# atom-hub-proto-self-Vorlage.net
KiCad netlist of a schematic drawn in EAGLE
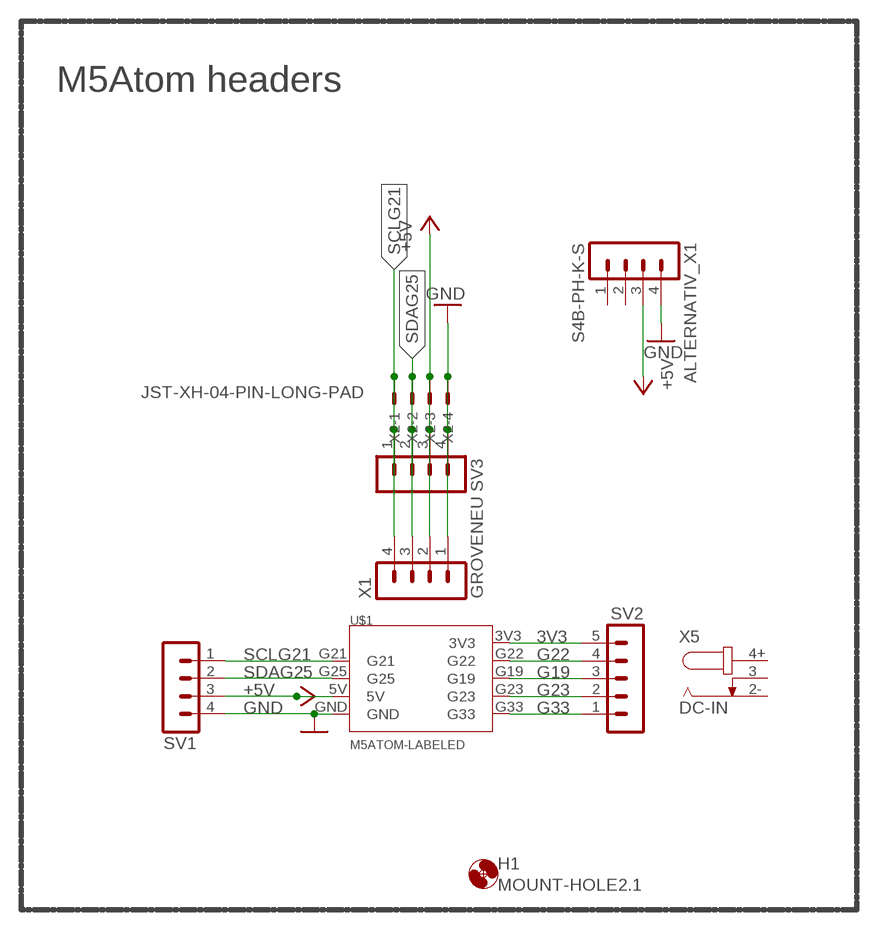
[diagram p0: schematic, sheet 1]

(export (version "E")
  (design (tool "Eeschema 10.0.6"))
  (components
    (comp (ref "ALTERNATIV_X1")
      (value "S4B-PH-K-S")
      (footprint "eagle-import:S4B-PH-K-S")
      (libsource (lib "eagle-import") (part "S4B-PH-K-S"))
    )
    (comp (ref "H1")
      (value "MOUNT-HOLE2.1")
      (footprint "eagle-import:2,1")
      (libsource (lib "eagle-import") (part "MOUNT-HOLE2.1"))
    )
    (comp (ref "SV1")
      (value "MA04-1")
      (footprint "eagle-import:MA04-1")
      (libsource (lib "eagle-import") (part "MA04-1"))
    )
    (comp (ref "SV2")
      (value "MA05-1")
      (footprint "eagle-import:MA05-1")
      (libsource (lib "eagle-import") (part "MA05-1"))
    )
    (comp (ref "SV3")
      (value "MA04-1")
      (footprint "eagle-import:MA04-1")
      (libsource (lib "eagle-import") (part "MA04-1"))
    )
    (comp (ref "U$1")
      (value "M5ATOM-LABELED")
      (footprint "eagle-import:M5ATOM-W_-LABELS")
      (libsource (lib "eagle-import") (part "M5ATOM-LABELED"))
    )
    (comp (ref "X1")
      (value "GROVENEU")
      (footprint "eagle-import:GROVE-NEU")
      (libsource (lib "eagle-import") (part "GROVENEU"))
    )
    (comp (ref "X2")
      (value "JST-XH-04-PIN-LONG-PAD")
      (footprint "eagle-import:JST-XH-04-PACKAGE-LONG-PAD")
      (libsource (lib "eagle-import") (part "JST-XH-04-PIN-LONG-PAD"))
    )
    (comp (ref "X5")
      (value "DC-IN")
      (footprint "eagle-import:DC-IN-TH_DC-0440-2.5A-2.0")
      (libsource (lib "eagle-import") (part "DC-IN"))
    )
  )
  (nets
    (net (code "1") (name "+5V") (class "Default")
      (node (ref "ALTERNATIV_X1") (pin "3") (pinfunction "3_3") (pintype "passive"))
      (node (ref "SV1") (pin "3") (pinfunction "3_3") (pintype "passive"))
      (node (ref "SV3") (pin "3") (pinfunction "3_3") (pintype "passive"))
      (node (ref "U$1") (pin "5V") (pinfunction "5V_5V") (pintype "bidirectional"))
      (node (ref "X1") (pin "2") (pinfunction "2_2") (pintype "passive"))
      (node (ref "X2") (pin "3") (pinfunction "S_3") (pintype "passive"))
    )
    (net (code "2") (name "/3V3") (class "Default")
      (node (ref "SV2") (pin "5") (pinfunction "5_5") (pintype "passive"))
      (node (ref "U$1") (pin "3V3") (pinfunction "3V3_3V3") (pintype "bidirectional"))
    )
    (net (code "3") (name "/G19") (class "Default")
      (node (ref "SV2") (pin "3") (pinfunction "3_3") (pintype "passive"))
      (node (ref "U$1") (pin "G19") (pinfunction "G19_G19") (pintype "bidirectional"))
    )
    (net (code "4") (name "/G22") (class "Default")
      (node (ref "SV2") (pin "4") (pinfunction "4_4") (pintype "passive"))
      (node (ref "U$1") (pin "G22") (pinfunction "G22_G22") (pintype "bidirectional"))
    )
    (net (code "5") (name "/G23") (class "Default")
      (node (ref "SV2") (pin "2") (pinfunction "2_2") (pintype "passive"))
      (node (ref "U$1") (pin "G23") (pinfunction "G23_G23") (pintype "bidirectional"))
    )
    (net (code "6") (name "/G33") (class "Default")
      (node (ref "SV2") (pin "1") (pinfunction "1_1") (pintype "passive"))
      (node (ref "U$1") (pin "G33") (pinfunction "G33_G33") (pintype "bidirectional"))
    )
    (net (code "7") (name "GND") (class "Default")
      (node (ref "ALTERNATIV_X1") (pin "4") (pinfunction "4_4") (pintype "passive"))
      (node (ref "SV1") (pin "4") (pinfunction "4_4") (pintype "passive"))
      (node (ref "SV3") (pin "4") (pinfunction "4_4") (pintype "passive"))
      (node (ref "U$1") (pin "GND") (pinfunction "GND_GND") (pintype "bidirectional"))
      (node (ref "X1") (pin "1") (pinfunction "1_1") (pintype "passive"))
      (node (ref "X2") (pin "4") (pinfunction "S_4") (pintype "passive"))
    )
    (net (code "8") (name "SCLG21") (class "Default")
      (node (ref "SV1") (pin "1") (pinfunction "1_1") (pintype "passive"))
      (node (ref "SV3") (pin "1") (pinfunction "1_1") (pintype "passive"))
      (node (ref "U$1") (pin "G21") (pinfunction "G21_G21") (pintype "bidirectional"))
      (node (ref "X1") (pin "4") (pinfunction "4_4") (pintype "passive"))
      (node (ref "X2") (pin "1") (pinfunction "S_1") (pintype "passive"))
    )
    (net (code "9") (name "SDAG25") (class "Default")
      (node (ref "SV1") (pin "2") (pinfunction "2_2") (pintype "passive"))
      (node (ref "SV3") (pin "2") (pinfunction "2_2") (pintype "passive"))
      (node (ref "U$1") (pin "G25") (pinfunction "G25_G25") (pintype "bidirectional"))
      (node (ref "X1") (pin "3") (pinfunction "3_3") (pintype "passive"))
      (node (ref "X2") (pin "2") (pinfunction "S_2") (pintype "passive"))
    )
    (net (code "10") (name "unconnected-(ALTERNATIV_X1-Pad1)") (class "Default")
      (node (ref "ALTERNATIV_X1") (pin "1") (pinfunction "1_1") (pintype "passive"))
    )
    (net (code "11") (name "unconnected-(ALTERNATIV_X1-Pad2)") (class "Default")
      (node (ref "ALTERNATIV_X1") (pin "2") (pinfunction "2_2") (pintype "passive"))
    )
    (net (code "12") (name "unconnected-(X5-1-Pad2-)") (class "Default")
      (node (ref "X5") (pin "2-") (pinfunction "1_2-") (pintype "passive"))
    )
    (net (code "13") (name "unconnected-(X5-2-Pad3)") (class "Default")
      (node (ref "X5") (pin "3") (pinfunction "2_3") (pintype "passive"))
    )
    (net (code "14") (name "unconnected-(X5-3-Pad4+)") (class "Default")
      (node (ref "X5") (pin "4+") (pinfunction "3_4+") (pintype "passive"))
    )
  )
)
